# 6x5keyboard_v2_untested.net
KiCad netlist of a schematic drawn in EAGLE
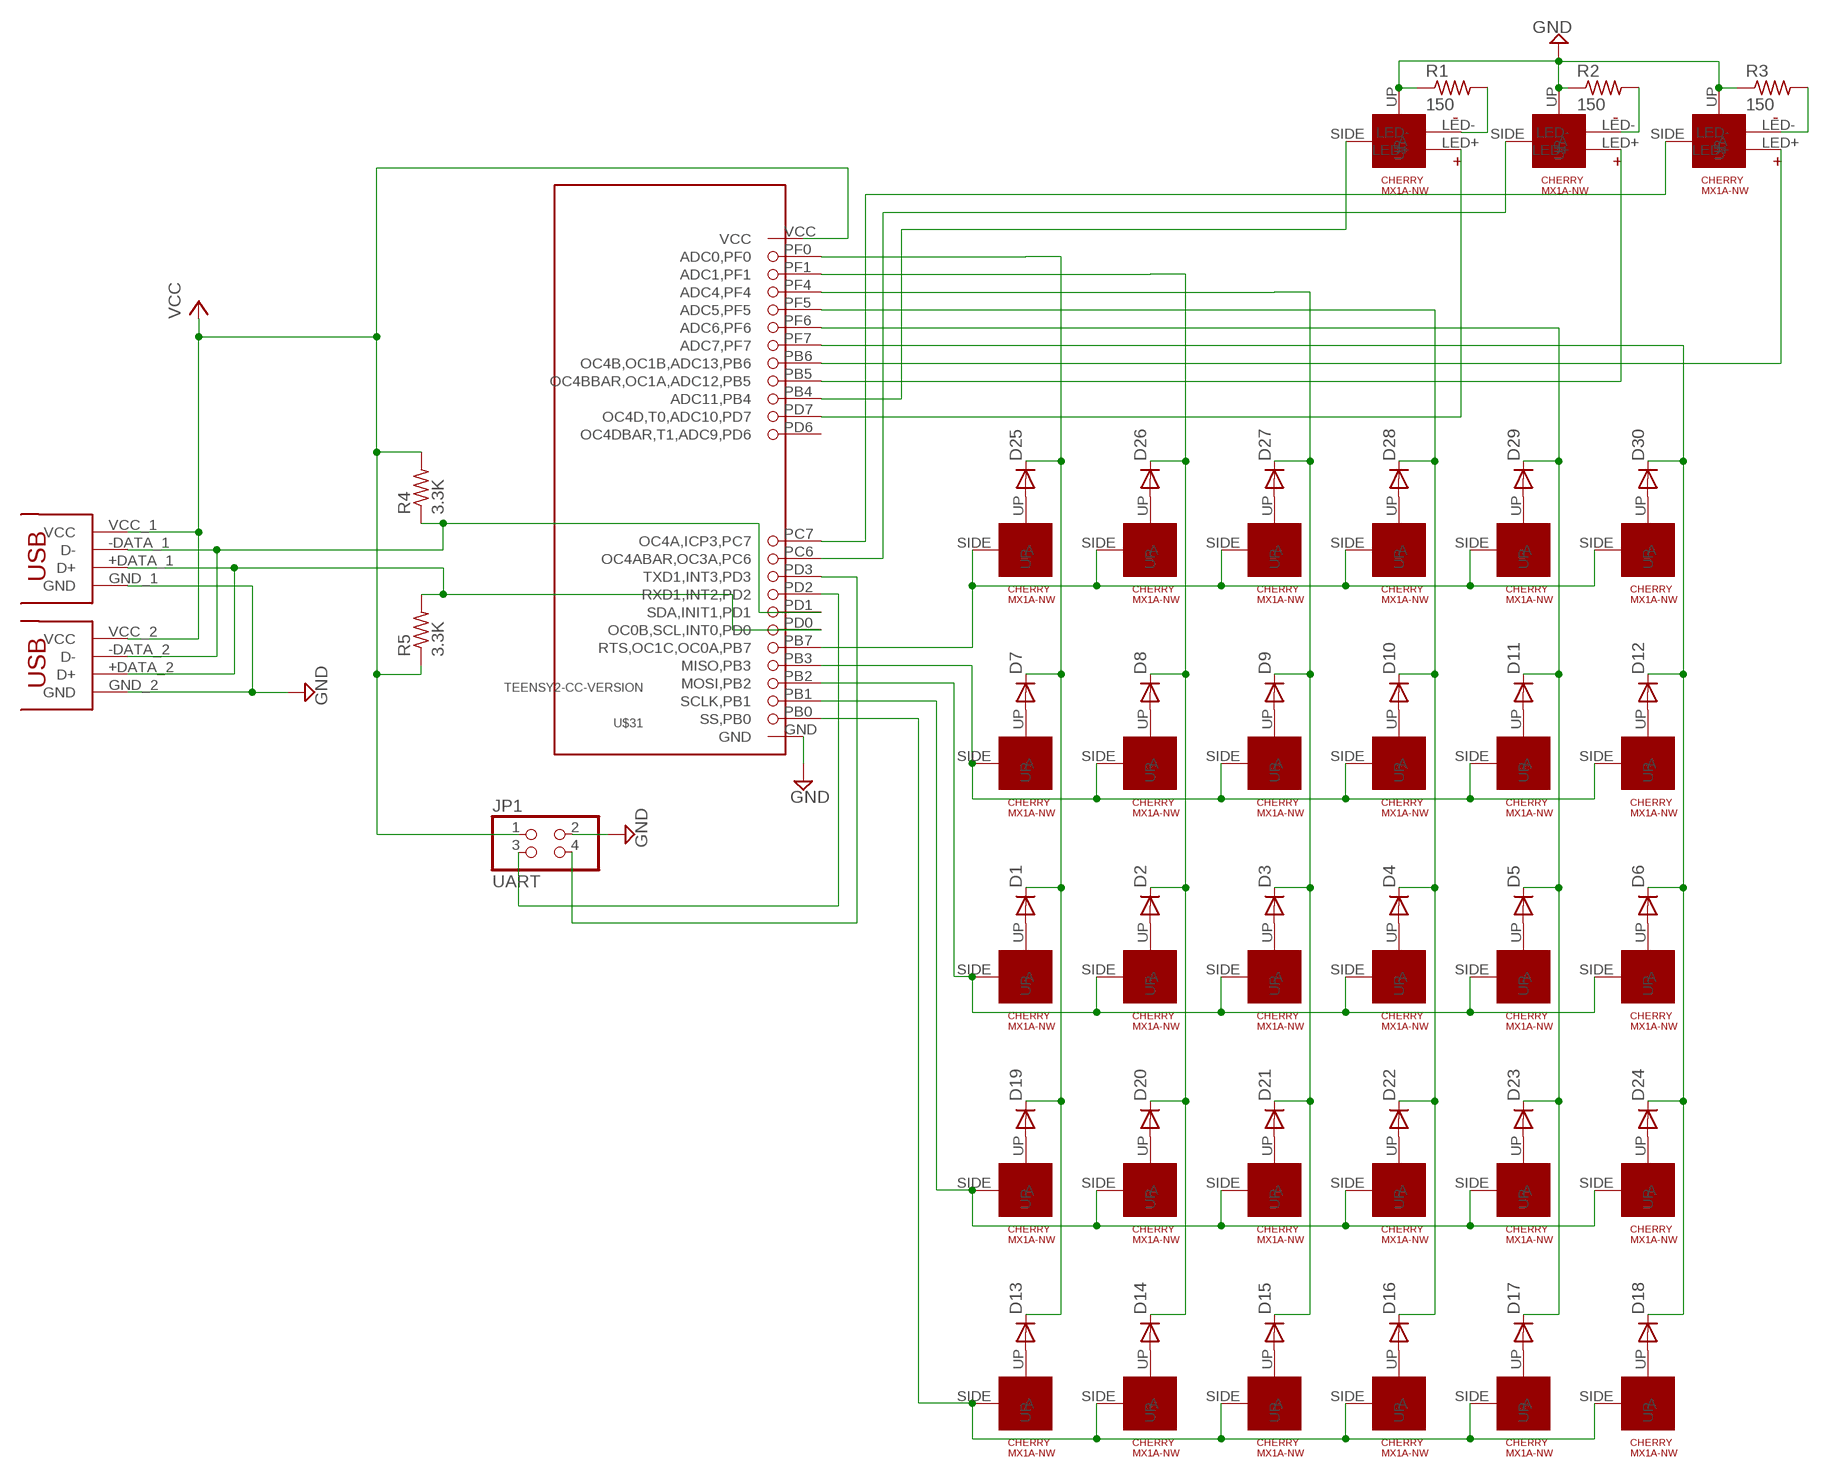
[diagram p0: schematic, sheet 1]

(export (version "E")
  (design (tool "Eeschema 10.0.6"))
  (components
    (comp (ref "D1")
      (value "1N4148DO35-7")
      (footprint "eagle-import:DO35-7")
      (libsource (lib "eagle-import") (part "1N4148DO35-7"))
    )
    (comp (ref "D2")
      (value "1N4148DO35-7")
      (footprint "eagle-import:DO35-7")
      (libsource (lib "eagle-import") (part "1N4148DO35-7"))
    )
    (comp (ref "D3")
      (value "1N4148DO35-7")
      (footprint "eagle-import:DO35-7")
      (libsource (lib "eagle-import") (part "1N4148DO35-7"))
    )
    (comp (ref "D4")
      (value "1N4148DO35-7")
      (footprint "eagle-import:DO35-7")
      (libsource (lib "eagle-import") (part "1N4148DO35-7"))
    )
    (comp (ref "D5")
      (value "1N4148DO35-7")
      (footprint "eagle-import:DO35-7")
      (libsource (lib "eagle-import") (part "1N4148DO35-7"))
    )
    (comp (ref "D6")
      (value "1N4148DO35-7")
      (footprint "eagle-import:DO35-7")
      (libsource (lib "eagle-import") (part "1N4148DO35-7"))
    )
    (comp (ref "D7")
      (value "1N4148DO35-7")
      (footprint "eagle-import:DO35-7")
      (libsource (lib "eagle-import") (part "1N4148DO35-7"))
    )
    (comp (ref "D8")
      (value "1N4148DO35-7")
      (footprint "eagle-import:DO35-7")
      (libsource (lib "eagle-import") (part "1N4148DO35-7"))
    )
    (comp (ref "D9")
      (value "1N4148DO35-7")
      (footprint "eagle-import:DO35-7")
      (libsource (lib "eagle-import") (part "1N4148DO35-7"))
    )
    (comp (ref "D10")
      (value "1N4148DO35-7")
      (footprint "eagle-import:DO35-7")
      (libsource (lib "eagle-import") (part "1N4148DO35-7"))
    )
    (comp (ref "D11")
      (value "1N4148DO35-7")
      (footprint "eagle-import:DO35-7")
      (libsource (lib "eagle-import") (part "1N4148DO35-7"))
    )
    (comp (ref "D12")
      (value "1N4148DO35-7")
      (footprint "eagle-import:DO35-7")
      (libsource (lib "eagle-import") (part "1N4148DO35-7"))
    )
    (comp (ref "D13")
      (value "1N4148DO35-7")
      (footprint "eagle-import:DO35-7")
      (libsource (lib "eagle-import") (part "1N4148DO35-7"))
    )
    (comp (ref "D14")
      (value "1N4148DO35-7")
      (footprint "eagle-import:DO35-7")
      (libsource (lib "eagle-import") (part "1N4148DO35-7"))
    )
    (comp (ref "D15")
      (value "1N4148DO35-7")
      (footprint "eagle-import:DO35-7")
      (libsource (lib "eagle-import") (part "1N4148DO35-7"))
    )
    (comp (ref "D16")
      (value "1N4148DO35-7")
      (footprint "eagle-import:DO35-7")
      (libsource (lib "eagle-import") (part "1N4148DO35-7"))
    )
    (comp (ref "D17")
      (value "1N4148DO35-7")
      (footprint "eagle-import:DO35-7")
      (libsource (lib "eagle-import") (part "1N4148DO35-7"))
    )
    (comp (ref "D18")
      (value "1N4148DO35-7")
      (footprint "eagle-import:DO35-7")
      (libsource (lib "eagle-import") (part "1N4148DO35-7"))
    )
    (comp (ref "D19")
      (value "1N4148DO35-7")
      (footprint "eagle-import:DO35-7")
      (libsource (lib "eagle-import") (part "1N4148DO35-7"))
    )
    (comp (ref "D20")
      (value "1N4148DO35-7")
      (footprint "eagle-import:DO35-7")
      (libsource (lib "eagle-import") (part "1N4148DO35-7"))
    )
    (comp (ref "D21")
      (value "1N4148DO35-7")
      (footprint "eagle-import:DO35-7")
      (libsource (lib "eagle-import") (part "1N4148DO35-7"))
    )
    (comp (ref "D22")
      (value "1N4148DO35-7")
      (footprint "eagle-import:DO35-7")
      (libsource (lib "eagle-import") (part "1N4148DO35-7"))
    )
    (comp (ref "D23")
      (value "1N4148DO35-7")
      (footprint "eagle-import:DO35-7")
      (libsource (lib "eagle-import") (part "1N4148DO35-7"))
    )
    (comp (ref "D24")
      (value "1N4148DO35-7")
      (footprint "eagle-import:DO35-7")
      (libsource (lib "eagle-import") (part "1N4148DO35-7"))
    )
    (comp (ref "D25")
      (value "1N4148DO35-7")
      (footprint "eagle-import:DO35-7")
      (libsource (lib "eagle-import") (part "1N4148DO35-7"))
    )
    (comp (ref "D26")
      (value "1N4148DO35-7")
      (footprint "eagle-import:DO35-7")
      (libsource (lib "eagle-import") (part "1N4148DO35-7"))
    )
    (comp (ref "D27")
      (value "1N4148DO35-7")
      (footprint "eagle-import:DO35-7")
      (libsource (lib "eagle-import") (part "1N4148DO35-7"))
    )
    (comp (ref "D28")
      (value "1N4148DO35-7")
      (footprint "eagle-import:DO35-7")
      (libsource (lib "eagle-import") (part "1N4148DO35-7"))
    )
    (comp (ref "D29")
      (value "1N4148DO35-7")
      (footprint "eagle-import:DO35-7")
      (libsource (lib "eagle-import") (part "1N4148DO35-7"))
    )
    (comp (ref "D30")
      (value "1N4148DO35-7")
      (footprint "eagle-import:DO35-7")
      (libsource (lib "eagle-import") (part "1N4148DO35-7"))
    )
    (comp (ref "JP1")
      (value "UART")
      (footprint "eagle-import:2X02")
      (libsource (lib "eagle-import") (part "PINHD-2X2"))
    )
    (comp (ref "R1")
      (value "150")
      (footprint "eagle-import:0207_10")
      (libsource (lib "eagle-import") (part "R-US_0207/10"))
    )
    (comp (ref "R2")
      (value "150")
      (footprint "eagle-import:0207_10")
      (libsource (lib "eagle-import") (part "R-US_0207/10"))
    )
    (comp (ref "R3")
      (value "150")
      (footprint "eagle-import:0207_10")
      (libsource (lib "eagle-import") (part "R-US_0207/10"))
    )
    (comp (ref "R4")
      (value "3.3K")
      (footprint "eagle-import:0207_10")
      (libsource (lib "eagle-import") (part "resistor_R-US_0207/10"))
    )
    (comp (ref "R5")
      (value "3.3K")
      (footprint "eagle-import:0207_10")
      (libsource (lib "eagle-import") (part "resistor_R-US_0207/10"))
    )
    (comp (ref "U$1")
      (value "CHERRY-MX1A-E1NW")
      (footprint "eagle-import:CHERRYMX-NN")
      (libsource (lib "eagle-import") (part "CHERRY-MX1A-E1NW"))
    )
    (comp (ref "U$2")
      (value "CHERRY-MX1A-E1NW")
      (footprint "eagle-import:CHERRYMX-NN")
      (libsource (lib "eagle-import") (part "CHERRY-MX1A-E1NW"))
    )
    (comp (ref "U$3")
      (value "CHERRY-MX1A-E1NW")
      (footprint "eagle-import:CHERRYMX-NN")
      (libsource (lib "eagle-import") (part "CHERRY-MX1A-E1NW"))
    )
    (comp (ref "U$4")
      (value "CHERRY-MX1A-E1NW")
      (footprint "eagle-import:CHERRYMX-NN")
      (libsource (lib "eagle-import") (part "CHERRY-MX1A-E1NW"))
    )
    (comp (ref "U$5")
      (value "CHERRY-MX1A-E1NW")
      (footprint "eagle-import:CHERRYMX-NN")
      (libsource (lib "eagle-import") (part "CHERRY-MX1A-E1NW"))
    )
    (comp (ref "U$6")
      (value "CHERRY-MX1A-E1NW")
      (footprint "eagle-import:CHERRYMX-NN")
      (libsource (lib "eagle-import") (part "CHERRY-MX1A-E1NW"))
    )
    (comp (ref "U$7")
      (value "CHERRY-MX1A-E1NW")
      (footprint "eagle-import:CHERRYMX-NN")
      (libsource (lib "eagle-import") (part "CHERRY-MX1A-E1NW"))
    )
    (comp (ref "U$8")
      (value "CHERRY-MX1A-E1NW")
      (footprint "eagle-import:CHERRYMX-NN")
      (libsource (lib "eagle-import") (part "CHERRY-MX1A-E1NW"))
    )
    (comp (ref "U$9")
      (value "CHERRY-MX1A-E1NW")
      (footprint "eagle-import:CHERRYMX-NN")
      (libsource (lib "eagle-import") (part "CHERRY-MX1A-E1NW"))
    )
    (comp (ref "U$10")
      (value "CHERRY-MX1A-E1NW")
      (footprint "eagle-import:CHERRYMX-NN")
      (libsource (lib "eagle-import") (part "CHERRY-MX1A-E1NW"))
    )
    (comp (ref "U$11")
      (value "CHERRY-MX1A-E1NW")
      (footprint "eagle-import:CHERRYMX-NN")
      (libsource (lib "eagle-import") (part "CHERRY-MX1A-E1NW"))
    )
    (comp (ref "U$12")
      (value "CHERRY-MX1A-E1NW")
      (footprint "eagle-import:CHERRYMX-NN")
      (libsource (lib "eagle-import") (part "CHERRY-MX1A-E1NW"))
    )
    (comp (ref "U$13")
      (value "CHERRY-MX1A-E1NW")
      (footprint "eagle-import:CHERRYMX-NN")
      (libsource (lib "eagle-import") (part "CHERRY-MX1A-E1NW"))
    )
    (comp (ref "U$14")
      (value "CHERRY-MX1A-E1NW")
      (footprint "eagle-import:CHERRYMX-NN")
      (libsource (lib "eagle-import") (part "CHERRY-MX1A-E1NW"))
    )
    (comp (ref "U$15")
      (value "CHERRY-MX1A-E1NW")
      (footprint "eagle-import:CHERRYMX-NN")
      (libsource (lib "eagle-import") (part "CHERRY-MX1A-E1NW"))
    )
    (comp (ref "U$16")
      (value "CHERRY-MX1A-E1NW")
      (footprint "eagle-import:CHERRYMX-NN")
      (libsource (lib "eagle-import") (part "CHERRY-MX1A-E1NW"))
    )
    (comp (ref "U$17")
      (value "CHERRY-MX1A-E1NW")
      (footprint "eagle-import:CHERRYMX-NN")
      (libsource (lib "eagle-import") (part "CHERRY-MX1A-E1NW"))
    )
    (comp (ref "U$18")
      (value "CHERRY-MX1A-E1NW")
      (footprint "eagle-import:CHERRYMX-NN")
      (libsource (lib "eagle-import") (part "CHERRY-MX1A-E1NW"))
    )
    (comp (ref "U$19")
      (value "CHERRY-MX1A-E1NW")
      (footprint "eagle-import:CHERRYMX-NN")
      (libsource (lib "eagle-import") (part "CHERRY-MX1A-E1NW"))
    )
    (comp (ref "U$20")
      (value "CHERRY-MX1A-E1NW")
      (footprint "eagle-import:CHERRYMX-NN")
      (libsource (lib "eagle-import") (part "CHERRY-MX1A-E1NW"))
    )
    (comp (ref "U$21")
      (value "CHERRY-MX1A-E1NW")
      (footprint "eagle-import:CHERRYMX-NN")
      (libsource (lib "eagle-import") (part "CHERRY-MX1A-E1NW"))
    )
    (comp (ref "U$22")
      (value "CHERRY-MX1A-E1NW")
      (footprint "eagle-import:CHERRYMX-NN")
      (libsource (lib "eagle-import") (part "CHERRY-MX1A-E1NW"))
    )
    (comp (ref "U$23")
      (value "CHERRY-MX1A-E1NW")
      (footprint "eagle-import:CHERRYMX-NN")
      (libsource (lib "eagle-import") (part "CHERRY-MX1A-E1NW"))
    )
    (comp (ref "U$24")
      (value "CHERRY-MX1A-E1NW")
      (footprint "eagle-import:CHERRYMX-NN")
      (libsource (lib "eagle-import") (part "CHERRY-MX1A-E1NW"))
    )
    (comp (ref "U$25")
      (value "CHERRY-MX1A-E1NW")
      (footprint "eagle-import:CHERRYMX-NN")
      (libsource (lib "eagle-import") (part "CHERRY-MX1A-E1NW"))
    )
    (comp (ref "U$26")
      (value "CHERRY-MX1A-E1NW")
      (footprint "eagle-import:CHERRYMX-NN")
      (libsource (lib "eagle-import") (part "CHERRY-MX1A-E1NW"))
    )
    (comp (ref "U$27")
      (value "CHERRY-MX1A-E1NW")
      (footprint "eagle-import:CHERRYMX-NN")
      (libsource (lib "eagle-import") (part "CHERRY-MX1A-E1NW"))
    )
    (comp (ref "U$28")
      (value "CHERRY-MX1A-E1NW")
      (footprint "eagle-import:CHERRYMX-NN")
      (libsource (lib "eagle-import") (part "CHERRY-MX1A-E1NW"))
    )
    (comp (ref "U$29")
      (value "CHERRY-MX1A-E1NW")
      (footprint "eagle-import:CHERRYMX-NN")
      (libsource (lib "eagle-import") (part "CHERRY-MX1A-E1NW"))
    )
    (comp (ref "U$30")
      (value "CHERRY-MX1A-E1NW")
      (footprint "eagle-import:CHERRYMX-NN")
      (libsource (lib "eagle-import") (part "CHERRY-MX1A-E1NW"))
    )
    (comp (ref "U$31")
      (value "TEENSY2-CC-VERSION")
      (footprint "eagle-import:TEENSY2")
      (libsource (lib "eagle-import") (part "TEENSY2-CC-VERSION"))
    )
    (comp (ref "U$32")
      (value "CHERRY-MX1A-E1NW-LED")
      (footprint "eagle-import:CHERRYMX-NN-LED")
      (libsource (lib "eagle-import") (part "CHERRY-MX1A-E1NW-LED"))
    )
    (comp (ref "U$33")
      (value "CHERRY-MX1A-E1NW-LED")
      (footprint "eagle-import:CHERRYMX-NN-LED")
      (libsource (lib "eagle-import") (part "CHERRY-MX1A-E1NW-LED"))
    )
    (comp (ref "U$34")
      (value "CHERRY-MX1A-E1NW-LED")
      (footprint "eagle-import:CHERRYMX-NN-LED")
      (libsource (lib "eagle-import") (part "CHERRY-MX1A-E1NW-LED"))
    )
    (comp (ref "U$35")
      (value "DUAL-USB-A")
      (footprint "eagle-import:DUAL-USB-A")
      (libsource (lib "eagle-import") (part "DUAL-USB-A"))
    )
  )
  (nets
    (net (code "1") (name "GND") (class "Default")
      (node (ref "JP1") (pin "2") (pinfunction "2_2") (pintype "passive"))
      (node (ref "R1") (pin "1") (pinfunction "1_1") (pintype "passive"))
      (node (ref "R2") (pin "1") (pinfunction "1_1") (pintype "passive"))
      (node (ref "R3") (pin "1") (pinfunction "1_1") (pintype "passive"))
      (node (ref "U$31") (pin "GND") (pinfunction "GND_GND") (pintype "power_in"))
      (node (ref "U$32") (pin "UP") (pinfunction "UP_UP") (pintype "bidirectional"))
      (node (ref "U$33") (pin "UP") (pinfunction "UP_UP") (pintype "bidirectional"))
      (node (ref "U$34") (pin "UP") (pinfunction "UP_UP") (pintype "bidirectional"))
      (node (ref "U$35") (pin "GND_1") (pinfunction "GND_GND_1") (pintype "bidirectional"))
      (node (ref "U$35") (pin "GND_2") (pinfunction "GND_GND_2") (pintype "bidirectional"))
    )
    (net (code "2") (name "Net-(D1-PadA)") (class "Default")
      (node (ref "D1") (pin "A") (pinfunction "A_A") (pintype "passive"))
      (node (ref "U$2") (pin "UP") (pinfunction "UP_UP") (pintype "bidirectional"))
    )
    (net (code "3") (name "Net-(D2-PadA)") (class "Default")
      (node (ref "D2") (pin "A") (pinfunction "A_A") (pintype "passive"))
      (node (ref "U$1") (pin "UP") (pinfunction "UP_UP") (pintype "bidirectional"))
    )
    (net (code "4") (name "Net-(D3-PadA)") (class "Default")
      (node (ref "D3") (pin "A") (pinfunction "A_A") (pintype "passive"))
      (node (ref "U$3") (pin "UP") (pinfunction "UP_UP") (pintype "bidirectional"))
    )
    (net (code "5") (name "Net-(D4-PadA)") (class "Default")
      (node (ref "D4") (pin "A") (pinfunction "A_A") (pintype "passive"))
      (node (ref "U$4") (pin "UP") (pinfunction "UP_UP") (pintype "bidirectional"))
    )
    (net (code "6") (name "Net-(D5-PadA)") (class "Default")
      (node (ref "D5") (pin "A") (pinfunction "A_A") (pintype "passive"))
      (node (ref "U$5") (pin "UP") (pinfunction "UP_UP") (pintype "bidirectional"))
    )
    (net (code "7") (name "Net-(D6-PadA)") (class "Default")
      (node (ref "D6") (pin "A") (pinfunction "A_A") (pintype "passive"))
      (node (ref "U$6") (pin "UP") (pinfunction "UP_UP") (pintype "bidirectional"))
    )
    (net (code "8") (name "Net-(D7-PadA)") (class "Default")
      (node (ref "D7") (pin "A") (pinfunction "A_A") (pintype "passive"))
      (node (ref "U$7") (pin "UP") (pinfunction "UP_UP") (pintype "bidirectional"))
    )
    (net (code "9") (name "Net-(D8-PadA)") (class "Default")
      (node (ref "D8") (pin "A") (pinfunction "A_A") (pintype "passive"))
      (node (ref "U$8") (pin "UP") (pinfunction "UP_UP") (pintype "bidirectional"))
    )
    (net (code "10") (name "Net-(D9-PadA)") (class "Default")
      (node (ref "D9") (pin "A") (pinfunction "A_A") (pintype "passive"))
      (node (ref "U$9") (pin "UP") (pinfunction "UP_UP") (pintype "bidirectional"))
    )
    (net (code "11") (name "Net-(D10-PadA)") (class "Default")
      (node (ref "D10") (pin "A") (pinfunction "A_A") (pintype "passive"))
      (node (ref "U$10") (pin "UP") (pinfunction "UP_UP") (pintype "bidirectional"))
    )
    (net (code "12") (name "Net-(D11-PadA)") (class "Default")
      (node (ref "D11") (pin "A") (pinfunction "A_A") (pintype "passive"))
      (node (ref "U$11") (pin "UP") (pinfunction "UP_UP") (pintype "bidirectional"))
    )
    (net (code "13") (name "Net-(D12-PadA)") (class "Default")
      (node (ref "D12") (pin "A") (pinfunction "A_A") (pintype "passive"))
      (node (ref "U$12") (pin "UP") (pinfunction "UP_UP") (pintype "bidirectional"))
    )
    (net (code "14") (name "Net-(D13-PadA)") (class "Default")
      (node (ref "D13") (pin "A") (pinfunction "A_A") (pintype "passive"))
      (node (ref "U$13") (pin "UP") (pinfunction "UP_UP") (pintype "bidirectional"))
    )
    (net (code "15") (name "Net-(D14-PadA)") (class "Default")
      (node (ref "D14") (pin "A") (pinfunction "A_A") (pintype "passive"))
      (node (ref "U$14") (pin "UP") (pinfunction "UP_UP") (pintype "bidirectional"))
    )
    (net (code "16") (name "Net-(D15-PadA)") (class "Default")
      (node (ref "D15") (pin "A") (pinfunction "A_A") (pintype "passive"))
      (node (ref "U$15") (pin "UP") (pinfunction "UP_UP") (pintype "bidirectional"))
    )
    (net (code "17") (name "Net-(D16-PadA)") (class "Default")
      (node (ref "D16") (pin "A") (pinfunction "A_A") (pintype "passive"))
      (node (ref "U$16") (pin "UP") (pinfunction "UP_UP") (pintype "bidirectional"))
    )
    (net (code "18") (name "Net-(D17-PadA)") (class "Default")
      (node (ref "D17") (pin "A") (pinfunction "A_A") (pintype "passive"))
      (node (ref "U$17") (pin "UP") (pinfunction "UP_UP") (pintype "bidirectional"))
    )
    (net (code "19") (name "Net-(D18-PadA)") (class "Default")
      (node (ref "D18") (pin "A") (pinfunction "A_A") (pintype "passive"))
      (node (ref "U$18") (pin "UP") (pinfunction "UP_UP") (pintype "bidirectional"))
    )
    (net (code "20") (name "Net-(D19-PadA)") (class "Default")
      (node (ref "D19") (pin "A") (pinfunction "A_A") (pintype "passive"))
      (node (ref "U$19") (pin "UP") (pinfunction "UP_UP") (pintype "bidirectional"))
    )
    (net (code "21") (name "Net-(D20-PadA)") (class "Default")
      (node (ref "D20") (pin "A") (pinfunction "A_A") (pintype "passive"))
      (node (ref "U$20") (pin "UP") (pinfunction "UP_UP") (pintype "bidirectional"))
    )
    (net (code "22") (name "Net-(D21-PadA)") (class "Default")
      (node (ref "D21") (pin "A") (pinfunction "A_A") (pintype "passive"))
      (node (ref "U$21") (pin "UP") (pinfunction "UP_UP") (pintype "bidirectional"))
    )
    (net (code "23") (name "Net-(D22-PadA)") (class "Default")
      (node (ref "D22") (pin "A") (pinfunction "A_A") (pintype "passive"))
      (node (ref "U$22") (pin "UP") (pinfunction "UP_UP") (pintype "bidirectional"))
    )
    (net (code "24") (name "Net-(D23-PadA)") (class "Default")
      (node (ref "D23") (pin "A") (pinfunction "A_A") (pintype "passive"))
      (node (ref "U$23") (pin "UP") (pinfunction "UP_UP") (pintype "bidirectional"))
    )
    (net (code "25") (name "Net-(D24-PadA)") (class "Default")
      (node (ref "D24") (pin "A") (pinfunction "A_A") (pintype "passive"))
      (node (ref "U$24") (pin "UP") (pinfunction "UP_UP") (pintype "bidirectional"))
    )
    (net (code "26") (name "Net-(D25-PadA)") (class "Default")
      (node (ref "D25") (pin "A") (pinfunction "A_A") (pintype "passive"))
      (node (ref "U$25") (pin "UP") (pinfunction "UP_UP") (pintype "bidirectional"))
    )
    (net (code "27") (name "Net-(D26-PadA)") (class "Default")
      (node (ref "D26") (pin "A") (pinfunction "A_A") (pintype "passive"))
      (node (ref "U$26") (pin "UP") (pinfunction "UP_UP") (pintype "bidirectional"))
    )
    (net (code "28") (name "Net-(D27-PadA)") (class "Default")
      (node (ref "D27") (pin "A") (pinfunction "A_A") (pintype "passive"))
      (node (ref "U$27") (pin "UP") (pinfunction "UP_UP") (pintype "bidirectional"))
    )
    (net (code "29") (name "Net-(D28-PadA)") (class "Default")
      (node (ref "D28") (pin "A") (pinfunction "A_A") (pintype "passive"))
      (node (ref "U$28") (pin "UP") (pinfunction "UP_UP") (pintype "bidirectional"))
    )
    (net (code "30") (name "Net-(D29-PadA)") (class "Default")
      (node (ref "D29") (pin "A") (pinfunction "A_A") (pintype "passive"))
      (node (ref "U$29") (pin "UP") (pinfunction "UP_UP") (pintype "bidirectional"))
    )
    (net (code "31") (name "Net-(D30-PadA)") (class "Default")
      (node (ref "D30") (pin "A") (pinfunction "A_A") (pintype "passive"))
      (node (ref "U$30") (pin "UP") (pinfunction "UP_UP") (pintype "bidirectional"))
    )
    (net (code "32") (name "Net-(R1-Pad2)") (class "Default")
      (node (ref "R1") (pin "2") (pinfunction "2_2") (pintype "passive"))
      (node (ref "U$32") (pin "LED-") (pinfunction "LED-_LED-") (pintype "bidirectional"))
    )
    (net (code "33") (name "Net-(R2-Pad2)") (class "Default")
      (node (ref "R2") (pin "2") (pinfunction "2_2") (pintype "passive"))
      (node (ref "U$33") (pin "LED-") (pinfunction "LED-_LED-") (pintype "bidirectional"))
    )
    (net (code "34") (name "Net-(R3-Pad2)") (class "Default")
      (node (ref "R3") (pin "2") (pinfunction "2_2") (pintype "passive"))
      (node (ref "U$34") (pin "LED-") (pinfunction "LED-_LED-") (pintype "bidirectional"))
    )
    (net (code "35") (name "Net-(U$1-A)") (class "Default")
      (node (ref "U$1") (pin "SIDE") (pinfunction "A_SIDE") (pintype "bidirectional"))
      (node (ref "U$2") (pin "SIDE") (pinfunction "A_SIDE") (pintype "bidirectional"))
      (node (ref "U$3") (pin "SIDE") (pinfunction "A_SIDE") (pintype "bidirectional"))
      (node (ref "U$31") (pin "PB2") (pinfunction "MOSI,PB2_PB2") (pintype "bidirectional"))
      (node (ref "U$4") (pin "SIDE") (pinfunction "A_SIDE") (pintype "bidirectional"))
      (node (ref "U$5") (pin "SIDE") (pinfunction "A_SIDE") (pintype "bidirectional"))
      (node (ref "U$6") (pin "SIDE") (pinfunction "A_SIDE") (pintype "bidirectional"))
    )
    (net (code "36") (name "Net-(U$10-A)") (class "Default")
      (node (ref "U$10") (pin "SIDE") (pinfunction "A_SIDE") (pintype "bidirectional"))
      (node (ref "U$11") (pin "SIDE") (pinfunction "A_SIDE") (pintype "bidirectional"))
      (node (ref "U$12") (pin "SIDE") (pinfunction "A_SIDE") (pintype "bidirectional"))
      (node (ref "U$31") (pin "PB3") (pinfunction "MISO,PB3_PB3") (pintype "bidirectional"))
      (node (ref "U$7") (pin "SIDE") (pinfunction "A_SIDE") (pintype "bidirectional"))
      (node (ref "U$8") (pin "SIDE") (pinfunction "A_SIDE") (pintype "bidirectional"))
      (node (ref "U$9") (pin "SIDE") (pinfunction "A_SIDE") (pintype "bidirectional"))
    )
    (net (code "37") (name "Net-(U$13-A)") (class "Default")
      (node (ref "U$13") (pin "SIDE") (pinfunction "A_SIDE") (pintype "bidirectional"))
      (node (ref "U$14") (pin "SIDE") (pinfunction "A_SIDE") (pintype "bidirectional"))
      (node (ref "U$15") (pin "SIDE") (pinfunction "A_SIDE") (pintype "bidirectional"))
      (node (ref "U$16") (pin "SIDE") (pinfunction "A_SIDE") (pintype "bidirectional"))
      (node (ref "U$17") (pin "SIDE") (pinfunction "A_SIDE") (pintype "bidirectional"))
      (node (ref "U$18") (pin "SIDE") (pinfunction "A_SIDE") (pintype "bidirectional"))
      (node (ref "U$31") (pin "PB0") (pinfunction "SS,PB0_PB0") (pintype "bidirectional"))
    )
    (net (code "38") (name "Net-(U$19-A)") (class "Default")
      (node (ref "U$19") (pin "SIDE") (pinfunction "A_SIDE") (pintype "bidirectional"))
      (node (ref "U$20") (pin "SIDE") (pinfunction "A_SIDE") (pintype "bidirectional"))
      (node (ref "U$21") (pin "SIDE") (pinfunction "A_SIDE") (pintype "bidirectional"))
      (node (ref "U$22") (pin "SIDE") (pinfunction "A_SIDE") (pintype "bidirectional"))
      (node (ref "U$23") (pin "SIDE") (pinfunction "A_SIDE") (pintype "bidirectional"))
      (node (ref "U$24") (pin "SIDE") (pinfunction "A_SIDE") (pintype "bidirectional"))
      (node (ref "U$31") (pin "PB1") (pinfunction "SCLK,PB1_PB1") (pintype "bidirectional"))
    )
    (net (code "39") (name "Net-(U$25-A)") (class "Default")
      (node (ref "U$25") (pin "SIDE") (pinfunction "A_SIDE") (pintype "bidirectional"))
      (node (ref "U$26") (pin "SIDE") (pinfunction "A_SIDE") (pintype "bidirectional"))
      (node (ref "U$27") (pin "SIDE") (pinfunction "A_SIDE") (pintype "bidirectional"))
      (node (ref "U$28") (pin "SIDE") (pinfunction "A_SIDE") (pintype "bidirectional"))
      (node (ref "U$29") (pin "SIDE") (pinfunction "A_SIDE") (pintype "bidirectional"))
      (node (ref "U$30") (pin "SIDE") (pinfunction "A_SIDE") (pintype "bidirectional"))
      (node (ref "U$31") (pin "PB7") (pinfunction "RTS,OC1C,OC0A,PB7_PB7") (pintype "bidirectional"))
    )
    (net (code "40") (name "Net-(U$31-ADC0,PF0)") (class "Default")
      (node (ref "D1") (pin "C") (pinfunction "C_C") (pintype "passive"))
      (node (ref "D13") (pin "C") (pinfunction "C_C") (pintype "passive"))
      (node (ref "D19") (pin "C") (pinfunction "C_C") (pintype "passive"))
      (node (ref "D25") (pin "C") (pinfunction "C_C") (pintype "passive"))
      (node (ref "D7") (pin "C") (pinfunction "C_C") (pintype "passive"))
      (node (ref "U$31") (pin "PF0") (pinfunction "ADC0,PF0_PF0") (pintype "bidirectional"))
    )
    (net (code "41") (name "Net-(U$31-ADC1,PF1)") (class "Default")
      (node (ref "D14") (pin "C") (pinfunction "C_C") (pintype "passive"))
      (node (ref "D2") (pin "C") (pinfunction "C_C") (pintype "passive"))
      (node (ref "D20") (pin "C") (pinfunction "C_C") (pintype "passive"))
      (node (ref "D26") (pin "C") (pinfunction "C_C") (pintype "passive"))
      (node (ref "D8") (pin "C") (pinfunction "C_C") (pintype "passive"))
      (node (ref "U$31") (pin "PF1") (pinfunction "ADC1,PF1_PF1") (pintype "bidirectional"))
    )
    (net (code "42") (name "Net-(U$31-ADC4,PF4)") (class "Default")
      (node (ref "D15") (pin "C") (pinfunction "C_C") (pintype "passive"))
      (node (ref "D21") (pin "C") (pinfunction "C_C") (pintype "passive"))
      (node (ref "D27") (pin "C") (pinfunction "C_C") (pintype "passive"))
      (node (ref "D3") (pin "C") (pinfunction "C_C") (pintype "passive"))
      (node (ref "D9") (pin "C") (pinfunction "C_C") (pintype "passive"))
      (node (ref "U$31") (pin "PF4") (pinfunction "ADC4,PF4_PF4") (pintype "bidirectional"))
    )
    (net (code "43") (name "Net-(U$31-ADC5,PF5)") (class "Default")
      (node (ref "D10") (pin "C") (pinfunction "C_C") (pintype "passive"))
      (node (ref "D16") (pin "C") (pinfunction "C_C") (pintype "passive"))
      (node (ref "D22") (pin "C") (pinfunction "C_C") (pintype "passive"))
      (node (ref "D28") (pin "C") (pinfunction "C_C") (pintype "passive"))
      (node (ref "D4") (pin "C") (pinfunction "C_C") (pintype "passive"))
      (node (ref "U$31") (pin "PF5") (pinfunction "ADC5,PF5_PF5") (pintype "bidirectional"))
    )
    (net (code "44") (name "Net-(U$31-ADC6,PF6)") (class "Default")
      (node (ref "D11") (pin "C") (pinfunction "C_C") (pintype "passive"))
      (node (ref "D17") (pin "C") (pinfunction "C_C") (pintype "passive"))
      (node (ref "D23") (pin "C") (pinfunction "C_C") (pintype "passive"))
      (node (ref "D29") (pin "C") (pinfunction "C_C") (pintype "passive"))
      (node (ref "D5") (pin "C") (pinfunction "C_C") (pintype "passive"))
      (node (ref "U$31") (pin "PF6") (pinfunction "ADC6,PF6_PF6") (pintype "bidirectional"))
    )
    (net (code "45") (name "Net-(U$31-ADC7,PF7)") (class "Default")
      (node (ref "D12") (pin "C") (pinfunction "C_C") (pintype "passive"))
      (node (ref "D18") (pin "C") (pinfunction "C_C") (pintype "passive"))
      (node (ref "D24") (pin "C") (pinfunction "C_C") (pintype "passive"))
      (node (ref "D30") (pin "C") (pinfunction "C_C") (pintype "passive"))
      (node (ref "D6") (pin "C") (pinfunction "C_C") (pintype "passive"))
      (node (ref "U$31") (pin "PF7") (pinfunction "ADC7,PF7_PF7") (pintype "bidirectional"))
    )
    (net (code "46") (name "Net-(U$31-ADC11,PB4)") (class "Default")
      (node (ref "U$31") (pin "PB4") (pinfunction "ADC11,PB4_PB4") (pintype "bidirectional"))
      (node (ref "U$32") (pin "SIDE") (pinfunction "A_SIDE") (pintype "bidirectional"))
    )
    (net (code "47") (name "Net-(U$31-OC0B,SCL,INT0,PD0)") (class "Default")
      (node (ref "R5") (pin "2") (pinfunction "2_2") (pintype "passive"))
      (node (ref "U$31") (pin "PD0") (pinfunction "OC0B,SCL,INT0,PD0_PD0") (pintype "bidirectional"))
      (node (ref "U$35") (pin "+DATA_1") (pinfunction "D+_+DATA_1") (pintype "bidirectional"))
      (node (ref "U$35") (pin "+DATA_2") (pinfunction "D+_+DATA_2") (pintype "bidirectional"))
    )
    (net (code "48") (name "Net-(U$31-OC4A,ICP3,PC7)") (class "Default")
      (node (ref "U$31") (pin "PC7") (pinfunction "OC4A,ICP3,PC7_PC7") (pintype "bidirectional"))
      (node (ref "U$34") (pin "SIDE") (pinfunction "A_SIDE") (pintype "bidirectional"))
    )
    (net (code "49") (name "Net-(U$31-OC4ABAR,OC3A,PC6)") (class "Default")
      (node (ref "U$31") (pin "PC6") (pinfunction "OC4ABAR,OC3A,PC6_PC6") (pintype "bidirectional"))
      (node (ref "U$33") (pin "SIDE") (pinfunction "A_SIDE") (pintype "bidirectional"))
    )
    (net (code "50") (name "Net-(U$31-OC4B,OC1B,ADC13,PB6)") (class "Default")
      (node (ref "U$31") (pin "PB6") (pinfunction "OC4B,OC1B,ADC13,PB6_PB6") (pintype "bidirectional"))
      (node (ref "U$34") (pin "LED+") (pinfunction "LED+_LED+") (pintype "bidirectional"))
    )
    (net (code "51") (name "Net-(U$31-OC4BBAR,OC1A,ADC12,PB5)") (class "Default")
      (node (ref "U$31") (pin "PB5") (pinfunction "OC4BBAR,OC1A,ADC12,PB5_PB5") (pintype "bidirectional"))
      (node (ref "U$33") (pin "LED+") (pinfunction "LED+_LED+") (pintype "bidirectional"))
    )
    (net (code "52") (name "Net-(U$31-OC4D,T0,ADC10,PD7)") (class "Default")
      (node (ref "U$31") (pin "PD7") (pinfunction "OC4D,T0,ADC10,PD7_PD7") (pintype "bidirectional"))
      (node (ref "U$32") (pin "LED+") (pinfunction "LED+_LED+") (pintype "bidirectional"))
    )
    (net (code "53") (name "Net-(U$31-RXD1,INT2,PD2)") (class "Default")
      (node (ref "JP1") (pin "3") (pinfunction "3_3") (pintype "passive"))
      (node (ref "U$31") (pin "PD2") (pinfunction "RXD1,INT2,PD2_PD2") (pintype "bidirectional"))
    )
    (net (code "54") (name "Net-(U$31-SDA,INIT1,PD1)") (class "Default")
      (node (ref "R4") (pin "1") (pinfunction "1_1") (pintype "passive"))
      (node (ref "U$31") (pin "PD1") (pinfunction "SDA,INIT1,PD1_PD1") (pintype "bidirectional"))
      (node (ref "U$35") (pin "-DATA_1") (pinfunction "D-_-DATA_1") (pintype "bidirectional"))
      (node (ref "U$35") (pin "-DATA_2") (pinfunction "D-_-DATA_2") (pintype "bidirectional"))
    )
    (net (code "55") (name "Net-(U$31-TXD1,INT3,PD3)") (class "Default")
      (node (ref "JP1") (pin "4") (pinfunction "4_4") (pintype "passive"))
      (node (ref "U$31") (pin "PD3") (pinfunction "TXD1,INT3,PD3_PD3") (pintype "bidirectional"))
    )
    (net (code "56") (name "VCC") (class "Default")
      (node (ref "JP1") (pin "1") (pinfunction "1_1") (pintype "passive"))
      (node (ref "R4") (pin "2") (pinfunction "2_2") (pintype "passive"))
      (node (ref "R5") (pin "1") (pinfunction "1_1") (pintype "passive"))
      (node (ref "U$31") (pin "VCC") (pinfunction "VCC_VCC") (pintype "power_in"))
      (node (ref "U$35") (pin "VCC_1") (pinfunction "VCC_VCC_1") (pintype "bidirectional"))
      (node (ref "U$35") (pin "VCC_2") (pinfunction "VCC_VCC_2") (pintype "bidirectional"))
    )
    (net (code "57") (name "unconnected-(U$31-OC4DBAR,T1,ADC9,PD6-PadPD6)") (class "Default")
      (node (ref "U$31") (pin "PD6") (pinfunction "OC4DBAR,T1,ADC9,PD6_PD6") (pintype "bidirectional"))
    )
  )
)
